# FRAM.net
KiCad netlist of a schematic drawn in Altium Designer
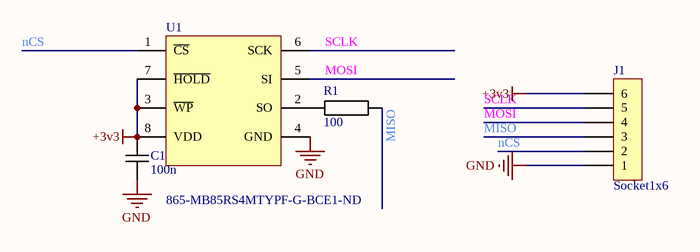
[diagram p0: FRAM.SchDoc]

(export (version "E")
  (design (tool "Eeschema 10.0.6"))
  (components
    (comp (ref "C1")
      (value "100n")
      (footprint "CAPACITOR 2012 REFLOW")
      (description "Capacitor")
      (libsource (lib "Capacitor") (part "Capacitor"))
    )
    (comp (ref "J1")
      (value "Socket1x6")
      (footprint "Socket1x6 P2.54")
      (description "Receptacle connector")
      (libsource (lib "PinHeader") (part "Socket1x6"))
    )
    (comp (ref "R1")
      (value "100")
      (footprint "RESISTOR 2012 REFLOW")
      (description "Resistor")
      (libsource (lib "Resistor") (part "Resistor"))
    )
    (comp (ref "U1")
      (value "865-MB85RS4MTYPF-G-BCE1-ND")
      (footprint "SO8W P1.27 C5.0X5.0 H2.0")
      (description "2-Mbit (256 K × 8) Serial (SPI) F-RAM")
      (libsource (lib "Memory") (part "FM25V20A-G"))
    )
  )
  (nets
    (net (code "1") (name "+3v3") (class "Default")
      (node (ref "C1") (pin "2") (pinfunction "2_2") (pintype "passive"))
      (node (ref "J1") (pin "6") (pinfunction "6_6") (pintype "passive"))
      (node (ref "U1") (pin "3") (pinfunction "~{WP}_3") (pintype "passive"))
      (node (ref "U1") (pin "7") (pinfunction "~{HOLD}_7") (pintype "passive"))
      (node (ref "U1") (pin "8") (pinfunction "VDD_8") (pintype "power_in"))
    )
    (net (code "2") (name "/MISO") (class "Default")
      (node (ref "J1") (pin "3") (pinfunction "3_3") (pintype "passive"))
      (node (ref "R1") (pin "2") (pinfunction "2_2") (pintype "passive"))
    )
    (net (code "3") (name "/MOSI") (class "Default")
      (node (ref "J1") (pin "4") (pinfunction "4_4") (pintype "passive"))
      (node (ref "U1") (pin "5") (pinfunction "SI_5") (pintype "passive"))
    )
    (net (code "4") (name "/SCLK") (class "Default")
      (node (ref "J1") (pin "5") (pinfunction "5_5") (pintype "passive"))
      (node (ref "U1") (pin "6") (pinfunction "SCK_6") (pintype "passive"))
    )
    (net (code "5") (name "/nCS") (class "Default")
      (node (ref "J1") (pin "2") (pinfunction "2_2") (pintype "passive"))
      (node (ref "U1") (pin "1") (pinfunction "~{CS}_1") (pintype "passive"))
    )
    (net (code "6") (name "GND") (class "Default")
      (node (ref "C1") (pin "1") (pinfunction "1_1") (pintype "passive"))
      (node (ref "J1") (pin "1") (pinfunction "1_1") (pintype "passive"))
      (node (ref "U1") (pin "4") (pinfunction "GND_4") (pintype "power_in"))
    )
    (net (code "7") (name "Net-(U1-SO)") (class "Default")
      (node (ref "R1") (pin "1") (pinfunction "1_1") (pintype "passive"))
      (node (ref "U1") (pin "2") (pinfunction "SO_2") (pintype "passive"))
    )
  )
)
